# SCH_moisture_sensor-rev_2021-10-16.net
KiCad netlist of a schematic drawn in EasyEDA
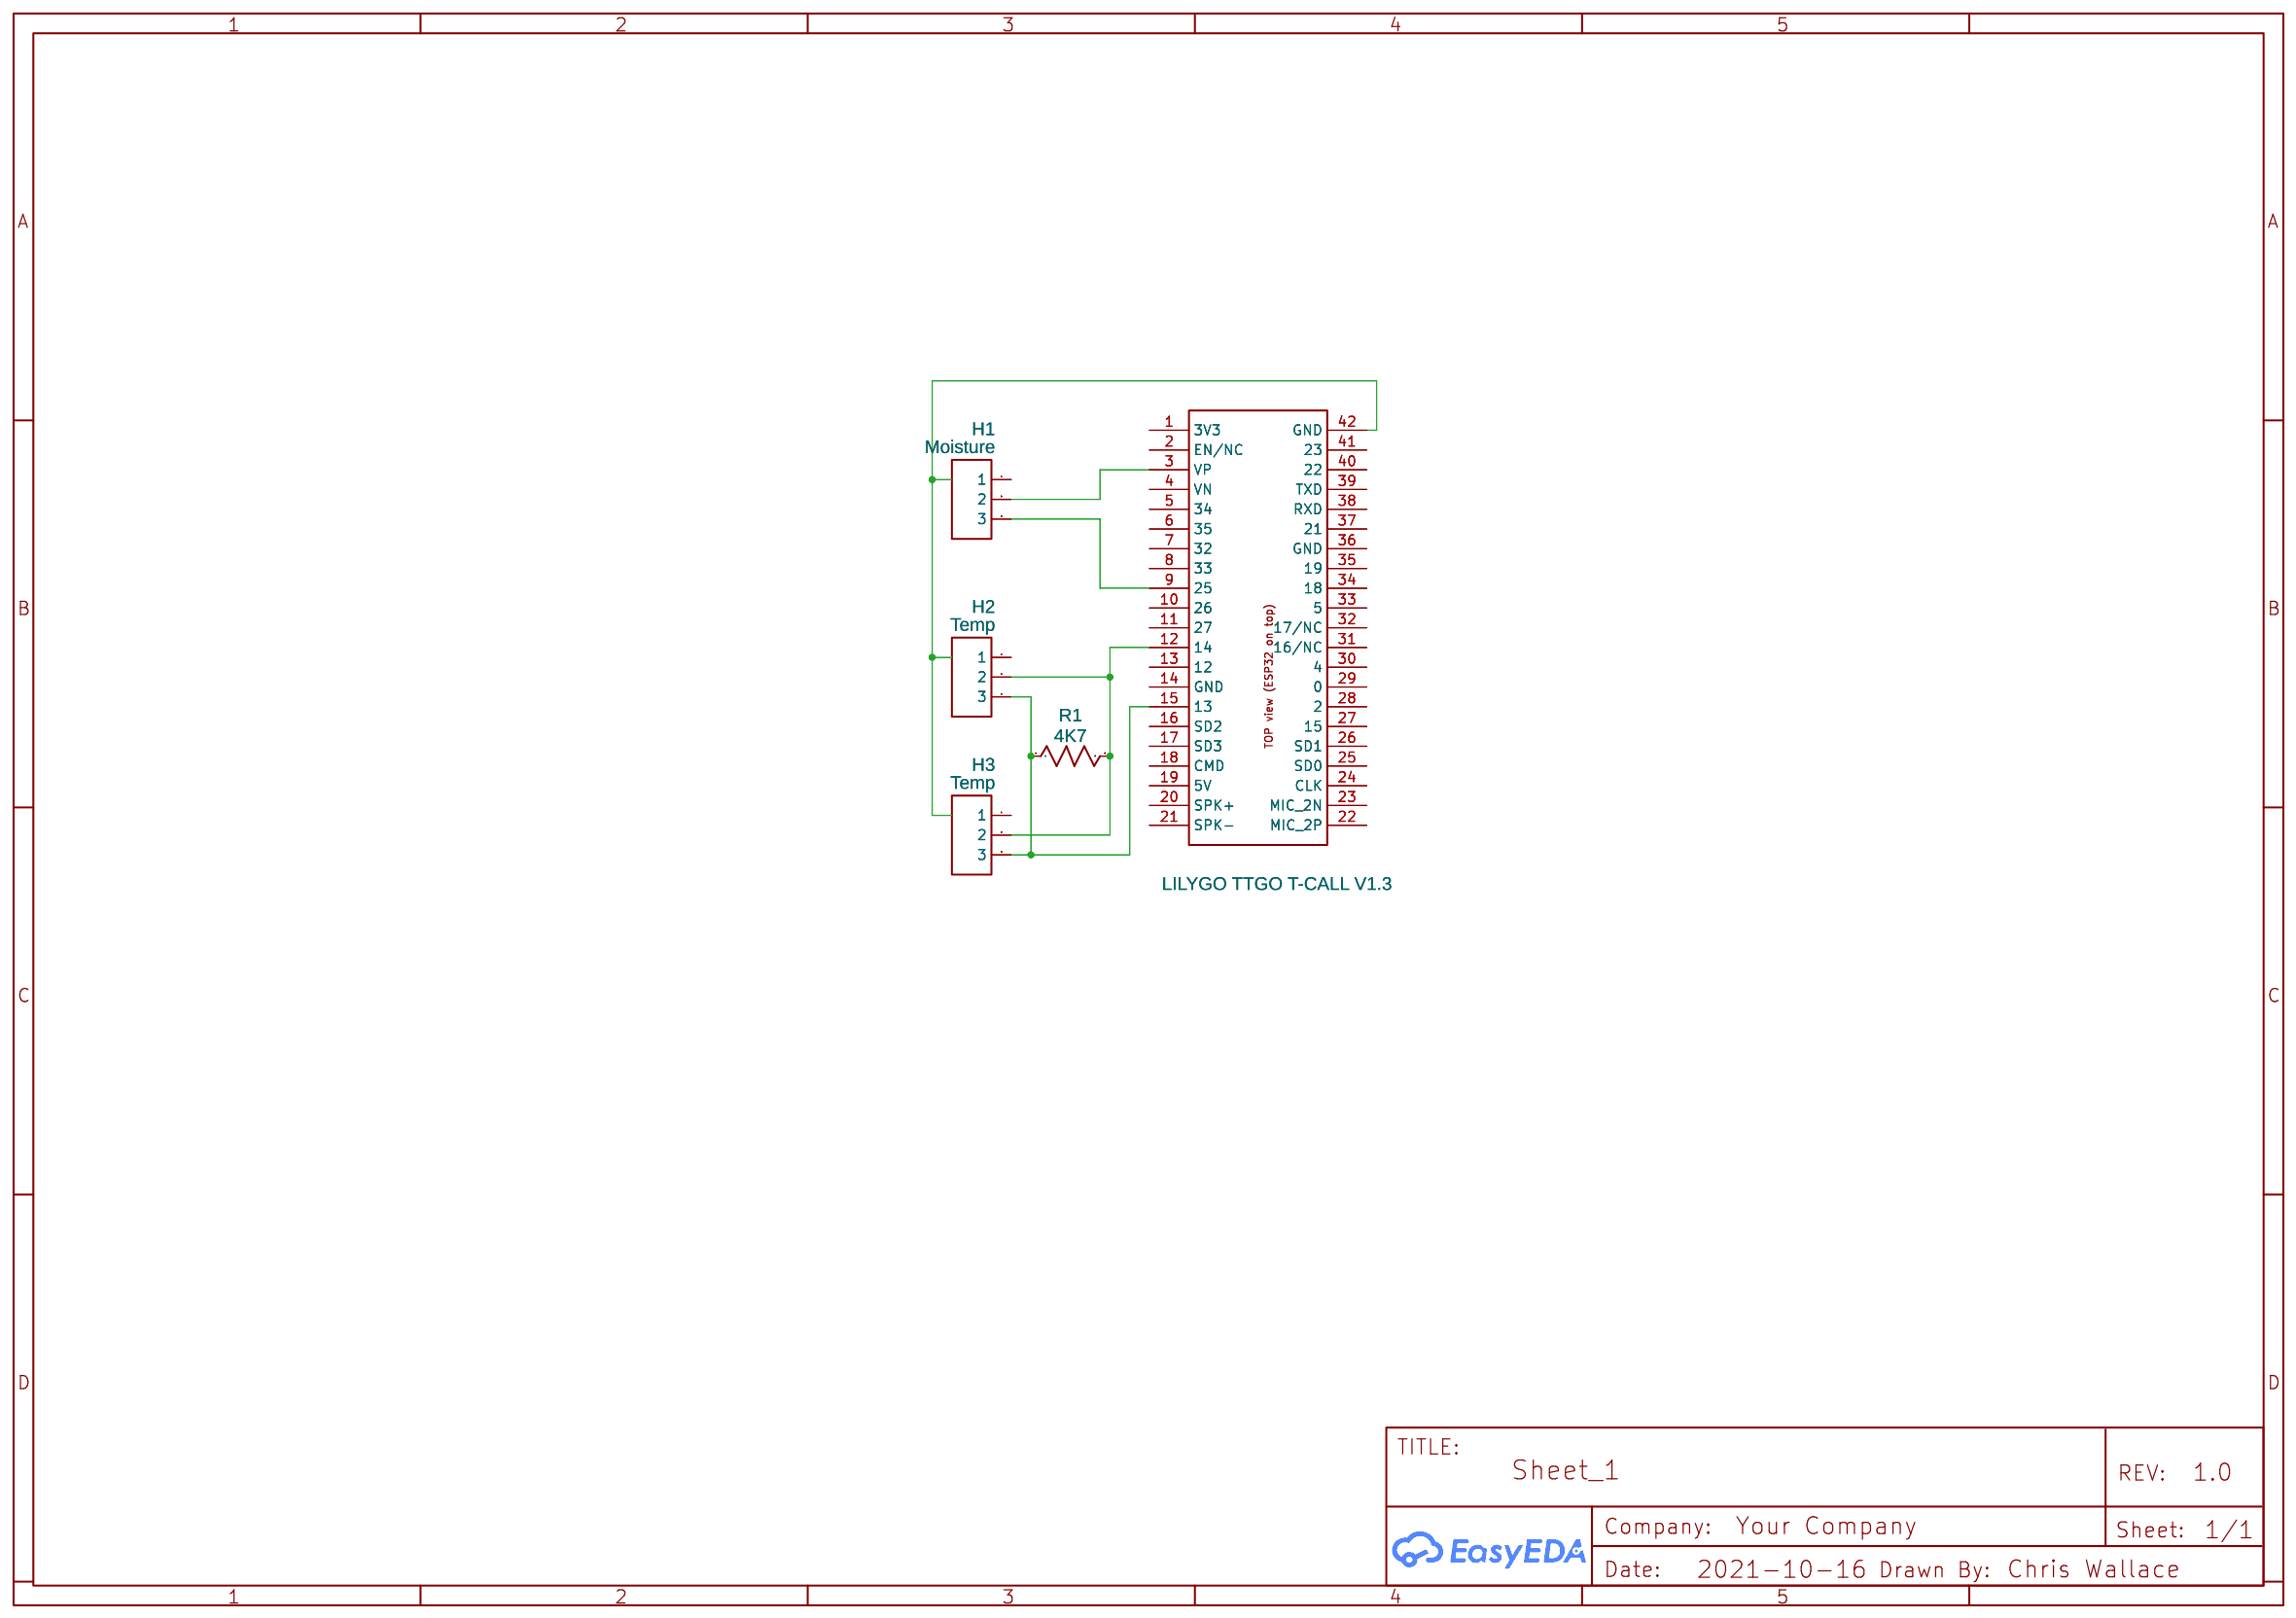
[diagram p0: schematic sheet]

(export (version "E")
  (design (tool "Eeschema 10.0.6"))
  (components
    (comp (ref "H1")
      (value "Moisture")
      (fields (field (name "BOM_Supplier Part") "C146690"))
      (libsource (lib "") (part "HDR-F-2.54_1x3"))
    )
    (comp (ref "H2")
      (value "Temp")
      (fields (field (name "BOM_Supplier Part") "C146690"))
      (libsource (lib "") (part "HDR-F-2.54_1x3"))
    )
    (comp (ref "H3")
      (value "Temp")
      (fields (field (name "BOM_Supplier Part") "C146690"))
      (libsource (lib "") (part "HDR-F-2.54_1x3"))
    )
    (comp (ref "R1") (value "4K7") (libsource (lib "") (part "R_0603_US")))
    (comp (ref "U1")
      (value "LILYGO TTGO T-CALL V1.3")
      (fields (field (name "BOM_Supplier Part") "T-Call v1.3 20190610"))
      (libsource (lib "") (part "LILYGO TTGO T-CALL V1.3"))
    )
  )
  (nets
    (net (code "1") (name "Net-(U1-13)") (class "Default")
      (node (ref "H2") (pin "3") (pinfunction "3_3") (pintype "input"))
      (node (ref "H3") (pin "3") (pinfunction "3_3") (pintype "input"))
      (node (ref "R1") (pin "1") (pinfunction "1_1") (pintype "unspecified"))
      (node (ref "U1") (pin "15") (pinfunction "13_15") (pintype "unspecified"))
    )
    (net (code "2") (name "Net-(U1-14)") (class "Default")
      (node (ref "H2") (pin "2") (pinfunction "2_2") (pintype "input"))
      (node (ref "H3") (pin "2") (pinfunction "2_2") (pintype "input"))
      (node (ref "R1") (pin "2") (pinfunction "2_2") (pintype "unspecified"))
      (node (ref "U1") (pin "12") (pinfunction "14_12") (pintype "unspecified"))
    )
    (net (code "3") (name "Net-(U1-25)") (class "Default")
      (node (ref "H1") (pin "3") (pinfunction "3_3") (pintype "input"))
      (node (ref "U1") (pin "9") (pinfunction "25_9") (pintype "unspecified"))
    )
    (net (code "4") (name "Net-(U1-VP)") (class "Default")
      (node (ref "H1") (pin "2") (pinfunction "2_2") (pintype "input"))
      (node (ref "U1") (pin "3") (pinfunction "VP_3") (pintype "unspecified"))
    )
    (net (code "5") (name "unconnected-(H1-Pad1)") (class "Default")
      (node (ref "H1") (pin "1") (pinfunction "1_1") (pintype "input"))
    )
    (net (code "6") (name "unconnected-(H2-Pad1)") (class "Default")
      (node (ref "H2") (pin "1") (pinfunction "1_1") (pintype "input"))
    )
    (net (code "7") (name "unconnected-(H3-Pad1)") (class "Default")
      (node (ref "H3") (pin "1") (pinfunction "1_1") (pintype "input"))
    )
    (net (code "8") (name "unconnected-(U1-0-Pad29)") (class "Default")
      (node (ref "U1") (pin "29") (pinfunction "0_29") (pintype "unspecified"))
    )
    (net (code "9") (name "unconnected-(U1-2-Pad28)") (class "Default")
      (node (ref "U1") (pin "28") (pinfunction "2_28") (pintype "unspecified"))
    )
    (net (code "10") (name "unconnected-(U1-3V3-Pad1)") (class "Default")
      (node (ref "U1") (pin "1") (pinfunction "3V3_1") (pintype "unspecified"))
    )
    (net (code "11") (name "unconnected-(U1-4-Pad30)") (class "Default")
      (node (ref "U1") (pin "30") (pinfunction "4_30") (pintype "unspecified"))
    )
    (net (code "12") (name "unconnected-(U1-5-Pad33)") (class "Default")
      (node (ref "U1") (pin "33") (pinfunction "5_33") (pintype "unspecified"))
    )
    (net (code "13") (name "unconnected-(U1-5V-Pad19)") (class "Default")
      (node (ref "U1") (pin "19") (pinfunction "5V_19") (pintype "unspecified"))
    )
    (net (code "14") (name "unconnected-(U1-12-Pad13)") (class "Default")
      (node (ref "U1") (pin "13") (pinfunction "12_13") (pintype "unspecified"))
    )
    (net (code "15") (name "unconnected-(U1-15-Pad27)") (class "Default")
      (node (ref "U1") (pin "27") (pinfunction "15_27") (pintype "unspecified"))
    )
    (net (code "16") (name "unconnected-(U1-16{slash}NC-Pad31)") (class "Default")
      (node (ref "U1") (pin "31") (pinfunction "16/NC_31") (pintype "unspecified"))
    )
    (net (code "17") (name "unconnected-(U1-17{slash}NC-Pad32)") (class "Default")
      (node (ref "U1") (pin "32") (pinfunction "17/NC_32") (pintype "unspecified"))
    )
    (net (code "18") (name "unconnected-(U1-18-Pad34)") (class "Default")
      (node (ref "U1") (pin "34") (pinfunction "18_34") (pintype "unspecified"))
    )
    (net (code "19") (name "unconnected-(U1-19-Pad35)") (class "Default")
      (node (ref "U1") (pin "35") (pinfunction "19_35") (pintype "unspecified"))
    )
    (net (code "20") (name "unconnected-(U1-21-Pad37)") (class "Default")
      (node (ref "U1") (pin "37") (pinfunction "21_37") (pintype "unspecified"))
    )
    (net (code "21") (name "unconnected-(U1-22-Pad40)") (class "Default")
      (node (ref "U1") (pin "40") (pinfunction "22_40") (pintype "unspecified"))
    )
    (net (code "22") (name "unconnected-(U1-23-Pad41)") (class "Default")
      (node (ref "U1") (pin "41") (pinfunction "23_41") (pintype "unspecified"))
    )
    (net (code "23") (name "unconnected-(U1-26-Pad10)") (class "Default")
      (node (ref "U1") (pin "10") (pinfunction "26_10") (pintype "unspecified"))
    )
    (net (code "24") (name "unconnected-(U1-27-Pad11)") (class "Default")
      (node (ref "U1") (pin "11") (pinfunction "27_11") (pintype "unspecified"))
    )
    (net (code "25") (name "unconnected-(U1-32-Pad7)") (class "Default")
      (node (ref "U1") (pin "7") (pinfunction "32_7") (pintype "unspecified"))
    )
    (net (code "26") (name "unconnected-(U1-33-Pad8)") (class "Default")
      (node (ref "U1") (pin "8") (pinfunction "33_8") (pintype "unspecified"))
    )
    (net (code "27") (name "unconnected-(U1-34-Pad5)") (class "Default")
      (node (ref "U1") (pin "5") (pinfunction "34_5") (pintype "unspecified"))
    )
    (net (code "28") (name "unconnected-(U1-35-Pad6)") (class "Default")
      (node (ref "U1") (pin "6") (pinfunction "35_6") (pintype "unspecified"))
    )
    (net (code "29") (name "unconnected-(U1-CLK-Pad24)") (class "Default")
      (node (ref "U1") (pin "24") (pinfunction "CLK_24") (pintype "unspecified"))
    )
    (net (code "30") (name "unconnected-(U1-CMD-Pad18)") (class "Default")
      (node (ref "U1") (pin "18") (pinfunction "CMD_18") (pintype "unspecified"))
    )
    (net (code "31") (name "unconnected-(U1-EN{slash}NC-Pad2)") (class "Default")
      (node (ref "U1") (pin "2") (pinfunction "EN/NC_2") (pintype "unspecified"))
    )
    (net (code "32") (name "unconnected-(U1-GND-Pad14)") (class "Default")
      (node (ref "U1") (pin "14") (pinfunction "GND_14") (pintype "unspecified"))
    )
    (net (code "33") (name "unconnected-(U1-GND-Pad36)") (class "Default")
      (node (ref "U1") (pin "36") (pinfunction "GND_36") (pintype "unspecified"))
    )
    (net (code "34") (name "unconnected-(U1-GND-Pad42)") (class "Default")
      (node (ref "U1") (pin "42") (pinfunction "GND_42") (pintype "unspecified"))
    )
    (net (code "35") (name "unconnected-(U1-MIC_2N-Pad23)") (class "Default")
      (node (ref "U1") (pin "23") (pinfunction "MIC_2N_23") (pintype "unspecified"))
    )
    (net (code "36") (name "unconnected-(U1-MIC_2P-Pad22)") (class "Default")
      (node (ref "U1") (pin "22") (pinfunction "MIC_2P_22") (pintype "unspecified"))
    )
    (net (code "37") (name "unconnected-(U1-RXD-Pad38)") (class "Default")
      (node (ref "U1") (pin "38") (pinfunction "RXD_38") (pintype "unspecified"))
    )
    (net (code "38") (name "unconnected-(U1-SD0-Pad25)") (class "Default")
      (node (ref "U1") (pin "25") (pinfunction "SD0_25") (pintype "unspecified"))
    )
    (net (code "39") (name "unconnected-(U1-SD1-Pad26)") (class "Default")
      (node (ref "U1") (pin "26") (pinfunction "SD1_26") (pintype "unspecified"))
    )
    (net (code "40") (name "unconnected-(U1-SD2-Pad16)") (class "Default")
      (node (ref "U1") (pin "16") (pinfunction "SD2_16") (pintype "unspecified"))
    )
    (net (code "41") (name "unconnected-(U1-SD3-Pad17)") (class "Default")
      (node (ref "U1") (pin "17") (pinfunction "SD3_17") (pintype "unspecified"))
    )
    (net (code "42") (name "unconnected-(U1-SPK+-Pad20)") (class "Default")
      (node (ref "U1") (pin "20") (pinfunction "SPK+_20") (pintype "unspecified"))
    )
    (net (code "43") (name "unconnected-(U1-SPK--Pad21)") (class "Default")
      (node (ref "U1") (pin "21") (pinfunction "SPK-_21") (pintype "unspecified"))
    )
    (net (code "44") (name "unconnected-(U1-TXD-Pad39)") (class "Default")
      (node (ref "U1") (pin "39") (pinfunction "TXD_39") (pintype "unspecified"))
    )
    (net (code "45") (name "unconnected-(U1-VN-Pad4)") (class "Default")
      (node (ref "U1") (pin "4") (pinfunction "VN_4") (pintype "unspecified"))
    )
  )
)
